# QuadroRiser.net
KiCad netlist of a schematic drawn in Altium Designer
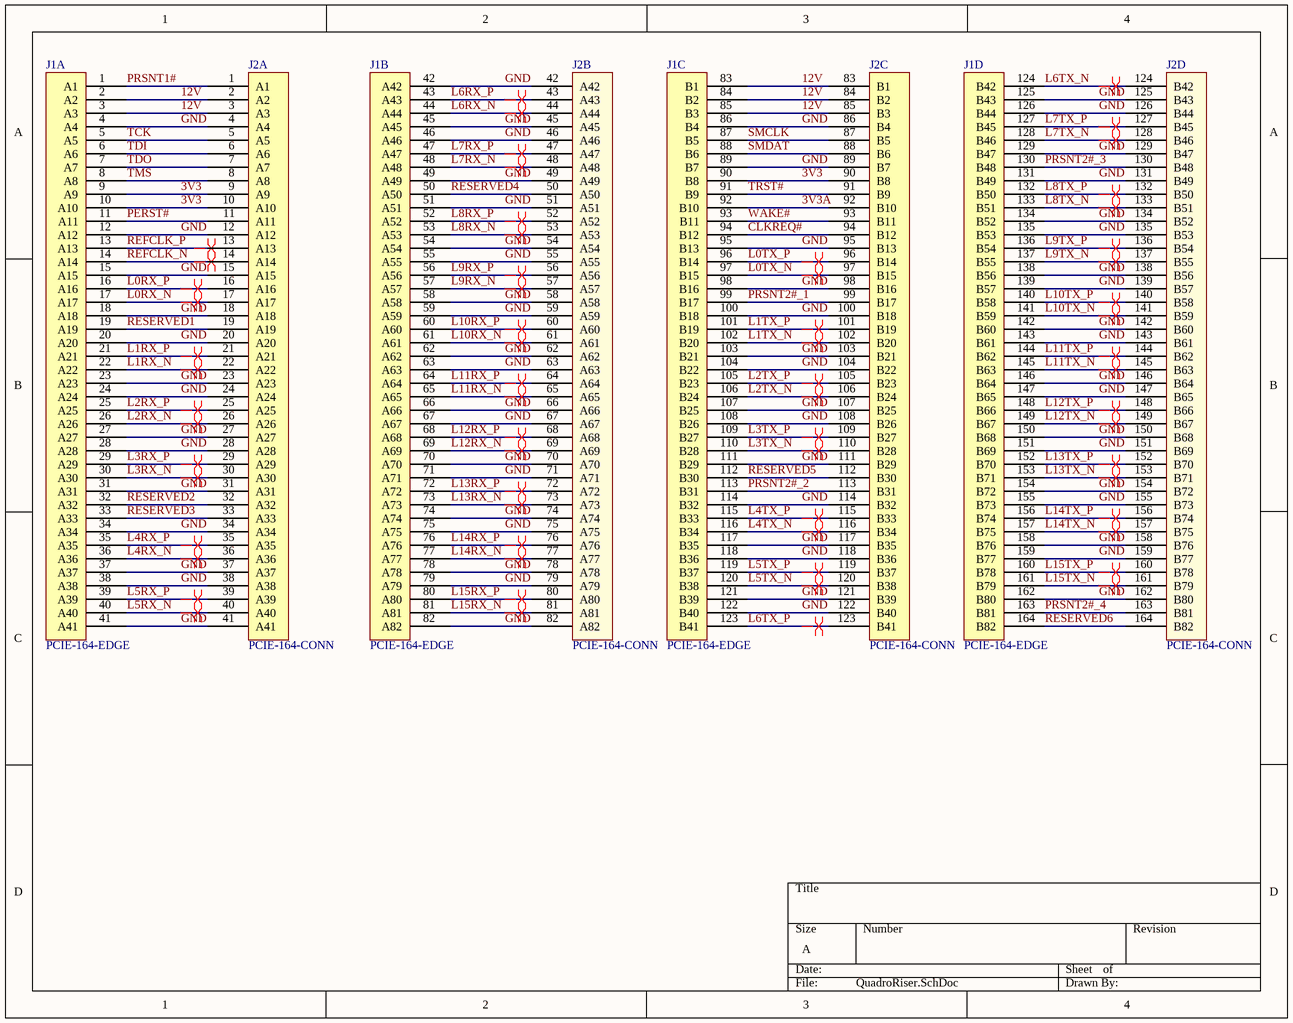
[diagram p0: QuadroRiser.SchDoc]

(export (version "E")
  (design (tool "Eeschema 10.0.6"))
  (components
    (comp (ref "J1")
      (value "PCIE-164-EDGE")
      (footprint "PCIE-164-EDGE")
      (description "PCIe x16 Edge Connector pad layout")
      (libsource (lib "") (part "PCIE-164-EDGE_1"))
    )
    (comp (ref "J2")
      (value "PCIE-164-CONN")
      (footprint "PCIe-164-CONN")
      (description "CONN PCI EXP FEMALE 164POS 0.039")
      (libsource (lib "Connectors") (part "PCIE-164-CONN"))
    )
  )
  (nets
    (net (code "1") (name "/3V3") (class "Default")
      (node (ref "J1") (pin "10") (pinfunction "A10_10") (pintype "passive"))
      (node (ref "J1") (pin "9") (pinfunction "A9_9") (pintype "passive"))
      (node (ref "J1") (pin "90") (pinfunction "B8_90") (pintype "passive"))
      (node (ref "J2") (pin "10") (pinfunction "A10_10") (pintype "passive"))
      (node (ref "J2") (pin "9") (pinfunction "A9_9") (pintype "passive"))
      (node (ref "J2") (pin "90") (pinfunction "B8_90") (pintype "passive"))
    )
    (net (code "2") (name "/3V3A") (class "Default")
      (node (ref "J1") (pin "92") (pinfunction "B10_92") (pintype "passive"))
      (node (ref "J2") (pin "92") (pinfunction "B10_92") (pintype "passive"))
    )
    (net (code "3") (name "/12V") (class "Default")
      (node (ref "J1") (pin "2") (pinfunction "A2_2") (pintype "passive"))
      (node (ref "J1") (pin "3") (pinfunction "A3_3") (pintype "passive"))
      (node (ref "J1") (pin "83") (pinfunction "B1_83") (pintype "passive"))
      (node (ref "J1") (pin "84") (pinfunction "B2_84") (pintype "passive"))
      (node (ref "J1") (pin "85") (pinfunction "B3_85") (pintype "passive"))
      (node (ref "J2") (pin "2") (pinfunction "A2_2") (pintype "passive"))
      (node (ref "J2") (pin "3") (pinfunction "A3_3") (pintype "passive"))
      (node (ref "J2") (pin "83") (pinfunction "B1_83") (pintype "passive"))
      (node (ref "J2") (pin "84") (pinfunction "B2_84") (pintype "passive"))
      (node (ref "J2") (pin "85") (pinfunction "B3_85") (pintype "passive"))
    )
    (net (code "4") (name "/CLKREQ#") (class "Default")
      (node (ref "J1") (pin "94") (pinfunction "B12_94") (pintype "passive"))
      (node (ref "J2") (pin "94") (pinfunction "B12_94") (pintype "passive"))
    )
    (net (code "5") (name "/GND") (class "Default")
      (node (ref "J1") (pin "100") (pinfunction "B18_100") (pintype "passive"))
      (node (ref "J1") (pin "103") (pinfunction "B21_103") (pintype "passive"))
      (node (ref "J1") (pin "104") (pinfunction "B22_104") (pintype "passive"))
      (node (ref "J1") (pin "107") (pinfunction "B25_107") (pintype "passive"))
      (node (ref "J1") (pin "108") (pinfunction "B26_108") (pintype "passive"))
      (node (ref "J1") (pin "111") (pinfunction "B29_111") (pintype "passive"))
      (node (ref "J1") (pin "114") (pinfunction "B32_114") (pintype "passive"))
      (node (ref "J1") (pin "117") (pinfunction "B35_117") (pintype "passive"))
      (node (ref "J1") (pin "118") (pinfunction "B36_118") (pintype "passive"))
      (node (ref "J1") (pin "12") (pinfunction "A12_12") (pintype "passive"))
      (node (ref "J1") (pin "121") (pinfunction "B39_121") (pintype "passive"))
      (node (ref "J1") (pin "122") (pinfunction "B40_122") (pintype "passive"))
      (node (ref "J1") (pin "125") (pinfunction "B43_125") (pintype "passive"))
      (node (ref "J1") (pin "126") (pinfunction "B44_126") (pintype "passive"))
      (node (ref "J1") (pin "129") (pinfunction "B47_129") (pintype "passive"))
      (node (ref "J1") (pin "131") (pinfunction "B49_131") (pintype "passive"))
      (node (ref "J1") (pin "134") (pinfunction "B52_134") (pintype "passive"))
      (node (ref "J1") (pin "135") (pinfunction "B53_135") (pintype "passive"))
      (node (ref "J1") (pin "138") (pinfunction "B56_138") (pintype "passive"))
      (node (ref "J1") (pin "139") (pinfunction "B57_139") (pintype "passive"))
      (node (ref "J1") (pin "142") (pinfunction "B60_142") (pintype "passive"))
      (node (ref "J1") (pin "143") (pinfunction "B61_143") (pintype "passive"))
      (node (ref "J1") (pin "146") (pinfunction "B64_146") (pintype "passive"))
      (node (ref "J1") (pin "147") (pinfunction "B65_147") (pintype "passive"))
      (node (ref "J1") (pin "15") (pinfunction "A15_15") (pintype "passive"))
      (node (ref "J1") (pin "150") (pinfunction "B68_150") (pintype "passive"))
      (node (ref "J1") (pin "151") (pinfunction "B69_151") (pintype "passive"))
      (node (ref "J1") (pin "154") (pinfunction "B72_154") (pintype "passive"))
      (node (ref "J1") (pin "155") (pinfunction "B73_155") (pintype "passive"))
      (node (ref "J1") (pin "158") (pinfunction "B76_158") (pintype "passive"))
      (node (ref "J1") (pin "159") (pinfunction "B77_159") (pintype "passive"))
      (node (ref "J1") (pin "162") (pinfunction "B80_162") (pintype "passive"))
      (node (ref "J1") (pin "18") (pinfunction "A18_18") (pintype "passive"))
      (node (ref "J1") (pin "20") (pinfunction "A20_20") (pintype "passive"))
      (node (ref "J1") (pin "23") (pinfunction "A23_23") (pintype "passive"))
      (node (ref "J1") (pin "24") (pinfunction "A24_24") (pintype "passive"))
      (node (ref "J1") (pin "27") (pinfunction "A27_27") (pintype "passive"))
      (node (ref "J1") (pin "28") (pinfunction "A28_28") (pintype "passive"))
      (node (ref "J1") (pin "31") (pinfunction "A31_31") (pintype "passive"))
      (node (ref "J1") (pin "34") (pinfunction "A34_34") (pintype "passive"))
      (node (ref "J1") (pin "37") (pinfunction "A37_37") (pintype "passive"))
      (node (ref "J1") (pin "38") (pinfunction "A38_38") (pintype "passive"))
      (node (ref "J1") (pin "4") (pinfunction "A4_4") (pintype "passive"))
      (node (ref "J1") (pin "41") (pinfunction "A41_41") (pintype "passive"))
      (node (ref "J1") (pin "42") (pinfunction "A42_42") (pintype "passive"))
      (node (ref "J1") (pin "45") (pinfunction "A45_45") (pintype "passive"))
      (node (ref "J1") (pin "46") (pinfunction "A46_46") (pintype "passive"))
      (node (ref "J1") (pin "49") (pinfunction "A49_49") (pintype "passive"))
      (node (ref "J1") (pin "51") (pinfunction "A51_51") (pintype "passive"))
      (node (ref "J1") (pin "54") (pinfunction "A54_54") (pintype "passive"))
      (node (ref "J1") (pin "55") (pinfunction "A55_55") (pintype "passive"))
      (node (ref "J1") (pin "58") (pinfunction "A58_58") (pintype "passive"))
      (node (ref "J1") (pin "59") (pinfunction "A59_59") (pintype "passive"))
      (node (ref "J1") (pin "62") (pinfunction "A62_62") (pintype "passive"))
      (node (ref "J1") (pin "63") (pinfunction "A63_63") (pintype "passive"))
      (node (ref "J1") (pin "66") (pinfunction "A66_66") (pintype "passive"))
      (node (ref "J1") (pin "67") (pinfunction "A67_67") (pintype "passive"))
      (node (ref "J1") (pin "70") (pinfunction "A70_70") (pintype "passive"))
      (node (ref "J1") (pin "71") (pinfunction "A71_71") (pintype "passive"))
      (node (ref "J1") (pin "74") (pinfunction "A74_74") (pintype "passive"))
      (node (ref "J1") (pin "75") (pinfunction "A75_75") (pintype "passive"))
      (node (ref "J1") (pin "78") (pinfunction "A78_78") (pintype "passive"))
      (node (ref "J1") (pin "79") (pinfunction "A79_79") (pintype "passive"))
      (node (ref "J1") (pin "82") (pinfunction "A82_82") (pintype "passive"))
      (node (ref "J1") (pin "86") (pinfunction "B4_86") (pintype "passive"))
      (node (ref "J1") (pin "89") (pinfunction "B7_89") (pintype "passive"))
      (node (ref "J1") (pin "95") (pinfunction "B13_95") (pintype "passive"))
      (node (ref "J1") (pin "98") (pinfunction "B16_98") (pintype "passive"))
      (node (ref "J2") (pin "100") (pinfunction "B18_100") (pintype "passive"))
      (node (ref "J2") (pin "103") (pinfunction "B21_103") (pintype "passive"))
      (node (ref "J2") (pin "104") (pinfunction "B22_104") (pintype "passive"))
      (node (ref "J2") (pin "107") (pinfunction "B25_107") (pintype "passive"))
      (node (ref "J2") (pin "108") (pinfunction "B26_108") (pintype "passive"))
      (node (ref "J2") (pin "111") (pinfunction "B29_111") (pintype "passive"))
      (node (ref "J2") (pin "114") (pinfunction "B32_114") (pintype "passive"))
      (node (ref "J2") (pin "117") (pinfunction "B35_117") (pintype "passive"))
      (node (ref "J2") (pin "118") (pinfunction "B36_118") (pintype "passive"))
      (node (ref "J2") (pin "12") (pinfunction "A12_12") (pintype "passive"))
      (node (ref "J2") (pin "121") (pinfunction "B39_121") (pintype "passive"))
      (node (ref "J2") (pin "122") (pinfunction "B40_122") (pintype "passive"))
      (node (ref "J2") (pin "125") (pinfunction "B43_125") (pintype "passive"))
      (node (ref "J2") (pin "126") (pinfunction "B44_126") (pintype "passive"))
      (node (ref "J2") (pin "129") (pinfunction "B47_129") (pintype "passive"))
      (node (ref "J2") (pin "131") (pinfunction "B49_131") (pintype "passive"))
      (node (ref "J2") (pin "134") (pinfunction "B52_134") (pintype "passive"))
      (node (ref "J2") (pin "135") (pinfunction "B53_135") (pintype "passive"))
      (node (ref "J2") (pin "138") (pinfunction "B56_138") (pintype "passive"))
      (node (ref "J2") (pin "139") (pinfunction "B57_139") (pintype "passive"))
      (node (ref "J2") (pin "142") (pinfunction "B60_142") (pintype "passive"))
      (node (ref "J2") (pin "143") (pinfunction "B61_143") (pintype "passive"))
      (node (ref "J2") (pin "146") (pinfunction "B64_146") (pintype "passive"))
      (node (ref "J2") (pin "147") (pinfunction "B65_147") (pintype "passive"))
      (node (ref "J2") (pin "15") (pinfunction "A15_15") (pintype "passive"))
      (node (ref "J2") (pin "150") (pinfunction "B68_150") (pintype "passive"))
      (node (ref "J2") (pin "151") (pinfunction "B69_151") (pintype "passive"))
      (node (ref "J2") (pin "154") (pinfunction "B72_154") (pintype "passive"))
      (node (ref "J2") (pin "155") (pinfunction "B73_155") (pintype "passive"))
      (node (ref "J2") (pin "158") (pinfunction "B76_158") (pintype "passive"))
      (node (ref "J2") (pin "159") (pinfunction "B77_159") (pintype "passive"))
      (node (ref "J2") (pin "162") (pinfunction "B80_162") (pintype "passive"))
      (node (ref "J2") (pin "18") (pinfunction "A18_18") (pintype "passive"))
      (node (ref "J2") (pin "20") (pinfunction "A20_20") (pintype "passive"))
      (node (ref "J2") (pin "23") (pinfunction "A23_23") (pintype "passive"))
      (node (ref "J2") (pin "24") (pinfunction "A24_24") (pintype "passive"))
      (node (ref "J2") (pin "27") (pinfunction "A27_27") (pintype "passive"))
      (node (ref "J2") (pin "28") (pinfunction "A28_28") (pintype "passive"))
      (node (ref "J2") (pin "31") (pinfunction "A31_31") (pintype "passive"))
      (node (ref "J2") (pin "34") (pinfunction "A34_34") (pintype "passive"))
      (node (ref "J2") (pin "37") (pinfunction "A37_37") (pintype "passive"))
      (node (ref "J2") (pin "38") (pinfunction "A38_38") (pintype "passive"))
      (node (ref "J2") (pin "4") (pinfunction "A4_4") (pintype "passive"))
      (node (ref "J2") (pin "41") (pinfunction "A41_41") (pintype "passive"))
      (node (ref "J2") (pin "42") (pinfunction "A42_42") (pintype "passive"))
      (node (ref "J2") (pin "45") (pinfunction "A45_45") (pintype "passive"))
      (node (ref "J2") (pin "46") (pinfunction "A46_46") (pintype "passive"))
      (node (ref "J2") (pin "49") (pinfunction "A49_49") (pintype "passive"))
      (node (ref "J2") (pin "51") (pinfunction "A51_51") (pintype "passive"))
      (node (ref "J2") (pin "54") (pinfunction "A54_54") (pintype "passive"))
      (node (ref "J2") (pin "55") (pinfunction "A55_55") (pintype "passive"))
      (node (ref "J2") (pin "58") (pinfunction "A58_58") (pintype "passive"))
      (node (ref "J2") (pin "59") (pinfunction "A59_59") (pintype "passive"))
      (node (ref "J2") (pin "62") (pinfunction "A62_62") (pintype "passive"))
      (node (ref "J2") (pin "63") (pinfunction "A63_63") (pintype "passive"))
      (node (ref "J2") (pin "66") (pinfunction "A66_66") (pintype "passive"))
      (node (ref "J2") (pin "67") (pinfunction "A67_67") (pintype "passive"))
      (node (ref "J2") (pin "70") (pinfunction "A70_70") (pintype "passive"))
      (node (ref "J2") (pin "71") (pinfunction "A71_71") (pintype "passive"))
      (node (ref "J2") (pin "74") (pinfunction "A74_74") (pintype "passive"))
      (node (ref "J2") (pin "75") (pinfunction "A75_75") (pintype "passive"))
      (node (ref "J2") (pin "78") (pinfunction "A78_78") (pintype "passive"))
      (node (ref "J2") (pin "79") (pinfunction "A79_79") (pintype "passive"))
      (node (ref "J2") (pin "82") (pinfunction "A82_82") (pintype "passive"))
      (node (ref "J2") (pin "86") (pinfunction "B4_86") (pintype "passive"))
      (node (ref "J2") (pin "89") (pinfunction "B7_89") (pintype "passive"))
      (node (ref "J2") (pin "95") (pinfunction "B13_95") (pintype "passive"))
      (node (ref "J2") (pin "98") (pinfunction "B16_98") (pintype "passive"))
    )
    (net (code "6") (name "/L0RX_N") (class "Default")
      (node (ref "J1") (pin "17") (pinfunction "A17_17") (pintype "passive"))
      (node (ref "J2") (pin "17") (pinfunction "A17_17") (pintype "passive"))
    )
    (net (code "7") (name "/L0RX_P") (class "Default")
      (node (ref "J1") (pin "16") (pinfunction "A16_16") (pintype "passive"))
      (node (ref "J2") (pin "16") (pinfunction "A16_16") (pintype "passive"))
    )
    (net (code "8") (name "/L0TX_N") (class "Default")
      (node (ref "J1") (pin "97") (pinfunction "B15_97") (pintype "passive"))
      (node (ref "J2") (pin "97") (pinfunction "B15_97") (pintype "passive"))
    )
    (net (code "9") (name "/L0TX_P") (class "Default")
      (node (ref "J1") (pin "96") (pinfunction "B14_96") (pintype "passive"))
      (node (ref "J2") (pin "96") (pinfunction "B14_96") (pintype "passive"))
    )
    (net (code "10") (name "/L1RX_N") (class "Default")
      (node (ref "J1") (pin "22") (pinfunction "A22_22") (pintype "passive"))
      (node (ref "J2") (pin "22") (pinfunction "A22_22") (pintype "passive"))
    )
    (net (code "11") (name "/L1RX_P") (class "Default")
      (node (ref "J1") (pin "21") (pinfunction "A21_21") (pintype "passive"))
      (node (ref "J2") (pin "21") (pinfunction "A21_21") (pintype "passive"))
    )
    (net (code "12") (name "/L1TX_N") (class "Default")
      (node (ref "J1") (pin "102") (pinfunction "B20_102") (pintype "passive"))
      (node (ref "J2") (pin "102") (pinfunction "B20_102") (pintype "passive"))
    )
    (net (code "13") (name "/L1TX_P") (class "Default")
      (node (ref "J1") (pin "101") (pinfunction "B19_101") (pintype "passive"))
      (node (ref "J2") (pin "101") (pinfunction "B19_101") (pintype "passive"))
    )
    (net (code "14") (name "/L2RX_N") (class "Default")
      (node (ref "J1") (pin "26") (pinfunction "A26_26") (pintype "passive"))
      (node (ref "J2") (pin "26") (pinfunction "A26_26") (pintype "passive"))
    )
    (net (code "15") (name "/L2RX_P") (class "Default")
      (node (ref "J1") (pin "25") (pinfunction "A25_25") (pintype "passive"))
      (node (ref "J2") (pin "25") (pinfunction "A25_25") (pintype "passive"))
    )
    (net (code "16") (name "/L2TX_N") (class "Default")
      (node (ref "J1") (pin "106") (pinfunction "B24_106") (pintype "passive"))
      (node (ref "J2") (pin "106") (pinfunction "B24_106") (pintype "passive"))
    )
    (net (code "17") (name "/L2TX_P") (class "Default")
      (node (ref "J1") (pin "105") (pinfunction "B23_105") (pintype "passive"))
      (node (ref "J2") (pin "105") (pinfunction "B23_105") (pintype "passive"))
    )
    (net (code "18") (name "/L3RX_N") (class "Default")
      (node (ref "J1") (pin "30") (pinfunction "A30_30") (pintype "passive"))
      (node (ref "J2") (pin "30") (pinfunction "A30_30") (pintype "passive"))
    )
    (net (code "19") (name "/L3RX_P") (class "Default")
      (node (ref "J1") (pin "29") (pinfunction "A29_29") (pintype "passive"))
      (node (ref "J2") (pin "29") (pinfunction "A29_29") (pintype "passive"))
    )
    (net (code "20") (name "/L3TX_N") (class "Default")
      (node (ref "J1") (pin "110") (pinfunction "B28_110") (pintype "passive"))
      (node (ref "J2") (pin "110") (pinfunction "B28_110") (pintype "passive"))
    )
    (net (code "21") (name "/L3TX_P") (class "Default")
      (node (ref "J1") (pin "109") (pinfunction "B27_109") (pintype "passive"))
      (node (ref "J2") (pin "109") (pinfunction "B27_109") (pintype "passive"))
    )
    (net (code "22") (name "/L4RX_N") (class "Default")
      (node (ref "J1") (pin "36") (pinfunction "A36_36") (pintype "passive"))
      (node (ref "J2") (pin "36") (pinfunction "A36_36") (pintype "passive"))
    )
    (net (code "23") (name "/L4RX_P") (class "Default")
      (node (ref "J1") (pin "35") (pinfunction "A35_35") (pintype "passive"))
      (node (ref "J2") (pin "35") (pinfunction "A35_35") (pintype "passive"))
    )
    (net (code "24") (name "/L4TX_N") (class "Default")
      (node (ref "J1") (pin "116") (pinfunction "B34_116") (pintype "passive"))
      (node (ref "J2") (pin "116") (pinfunction "B34_116") (pintype "passive"))
    )
    (net (code "25") (name "/L4TX_P") (class "Default")
      (node (ref "J1") (pin "115") (pinfunction "B33_115") (pintype "passive"))
      (node (ref "J2") (pin "115") (pinfunction "B33_115") (pintype "passive"))
    )
    (net (code "26") (name "/L5RX_N") (class "Default")
      (node (ref "J1") (pin "40") (pinfunction "A40_40") (pintype "passive"))
      (node (ref "J2") (pin "40") (pinfunction "A40_40") (pintype "passive"))
    )
    (net (code "27") (name "/L5RX_P") (class "Default")
      (node (ref "J1") (pin "39") (pinfunction "A39_39") (pintype "passive"))
      (node (ref "J2") (pin "39") (pinfunction "A39_39") (pintype "passive"))
    )
    (net (code "28") (name "/L5TX_N") (class "Default")
      (node (ref "J1") (pin "120") (pinfunction "B38_120") (pintype "passive"))
      (node (ref "J2") (pin "120") (pinfunction "B38_120") (pintype "passive"))
    )
    (net (code "29") (name "/L5TX_P") (class "Default")
      (node (ref "J1") (pin "119") (pinfunction "B37_119") (pintype "passive"))
      (node (ref "J2") (pin "119") (pinfunction "B37_119") (pintype "passive"))
    )
    (net (code "30") (name "/L6RX_N") (class "Default")
      (node (ref "J1") (pin "44") (pinfunction "A44_44") (pintype "passive"))
      (node (ref "J2") (pin "44") (pinfunction "A44_44") (pintype "passive"))
    )
    (net (code "31") (name "/L6RX_P") (class "Default")
      (node (ref "J1") (pin "43") (pinfunction "A43_43") (pintype "passive"))
      (node (ref "J2") (pin "43") (pinfunction "A43_43") (pintype "passive"))
    )
    (net (code "32") (name "/L6TX_N") (class "Default")
      (node (ref "J1") (pin "124") (pinfunction "B42_124") (pintype "passive"))
      (node (ref "J2") (pin "124") (pinfunction "B42_124") (pintype "passive"))
    )
    (net (code "33") (name "/L6TX_P") (class "Default")
      (node (ref "J1") (pin "123") (pinfunction "B41_123") (pintype "passive"))
      (node (ref "J2") (pin "123") (pinfunction "B41_123") (pintype "passive"))
    )
    (net (code "34") (name "/L7RX_N") (class "Default")
      (node (ref "J1") (pin "48") (pinfunction "A48_48") (pintype "passive"))
      (node (ref "J2") (pin "48") (pinfunction "A48_48") (pintype "passive"))
    )
    (net (code "35") (name "/L7RX_P") (class "Default")
      (node (ref "J1") (pin "47") (pinfunction "A47_47") (pintype "passive"))
      (node (ref "J2") (pin "47") (pinfunction "A47_47") (pintype "passive"))
    )
    (net (code "36") (name "/L7TX_N") (class "Default")
      (node (ref "J1") (pin "128") (pinfunction "B46_128") (pintype "passive"))
      (node (ref "J2") (pin "128") (pinfunction "B46_128") (pintype "passive"))
    )
    (net (code "37") (name "/L7TX_P") (class "Default")
      (node (ref "J1") (pin "127") (pinfunction "B45_127") (pintype "passive"))
      (node (ref "J2") (pin "127") (pinfunction "B45_127") (pintype "passive"))
    )
    (net (code "38") (name "/L8RX_N") (class "Default")
      (node (ref "J1") (pin "53") (pinfunction "A53_53") (pintype "passive"))
      (node (ref "J2") (pin "53") (pinfunction "A53_53") (pintype "passive"))
    )
    (net (code "39") (name "/L8RX_P") (class "Default")
      (node (ref "J1") (pin "52") (pinfunction "A52_52") (pintype "passive"))
      (node (ref "J2") (pin "52") (pinfunction "A52_52") (pintype "passive"))
    )
    (net (code "40") (name "/L8TX_N") (class "Default")
      (node (ref "J1") (pin "133") (pinfunction "B51_133") (pintype "passive"))
      (node (ref "J2") (pin "133") (pinfunction "B51_133") (pintype "passive"))
    )
    (net (code "41") (name "/L8TX_P") (class "Default")
      (node (ref "J1") (pin "132") (pinfunction "B50_132") (pintype "passive"))
      (node (ref "J2") (pin "132") (pinfunction "B50_132") (pintype "passive"))
    )
    (net (code "42") (name "/L9RX_N") (class "Default")
      (node (ref "J1") (pin "57") (pinfunction "A57_57") (pintype "passive"))
      (node (ref "J2") (pin "57") (pinfunction "A57_57") (pintype "passive"))
    )
    (net (code "43") (name "/L9RX_P") (class "Default")
      (node (ref "J1") (pin "56") (pinfunction "A56_56") (pintype "passive"))
      (node (ref "J2") (pin "56") (pinfunction "A56_56") (pintype "passive"))
    )
    (net (code "44") (name "/L9TX_N") (class "Default")
      (node (ref "J1") (pin "137") (pinfunction "B55_137") (pintype "passive"))
      (node (ref "J2") (pin "137") (pinfunction "B55_137") (pintype "passive"))
    )
    (net (code "45") (name "/L9TX_P") (class "Default")
      (node (ref "J1") (pin "136") (pinfunction "B54_136") (pintype "passive"))
      (node (ref "J2") (pin "136") (pinfunction "B54_136") (pintype "passive"))
    )
    (net (code "46") (name "/L10RX_N") (class "Default")
      (node (ref "J1") (pin "61") (pinfunction "A61_61") (pintype "passive"))
      (node (ref "J2") (pin "61") (pinfunction "A61_61") (pintype "passive"))
    )
    (net (code "47") (name "/L10RX_P") (class "Default")
      (node (ref "J1") (pin "60") (pinfunction "A60_60") (pintype "passive"))
      (node (ref "J2") (pin "60") (pinfunction "A60_60") (pintype "passive"))
    )
    (net (code "48") (name "/L10TX_N") (class "Default")
      (node (ref "J1") (pin "141") (pinfunction "B59_141") (pintype "passive"))
      (node (ref "J2") (pin "141") (pinfunction "B59_141") (pintype "passive"))
    )
    (net (code "49") (name "/L10TX_P") (class "Default")
      (node (ref "J1") (pin "140") (pinfunction "B58_140") (pintype "passive"))
      (node (ref "J2") (pin "140") (pinfunction "B58_140") (pintype "passive"))
    )
    (net (code "50") (name "/L11RX_N") (class "Default")
      (node (ref "J1") (pin "65") (pinfunction "A65_65") (pintype "passive"))
      (node (ref "J2") (pin "65") (pinfunction "A65_65") (pintype "passive"))
    )
    (net (code "51") (name "/L11RX_P") (class "Default")
      (node (ref "J1") (pin "64") (pinfunction "A64_64") (pintype "passive"))
      (node (ref "J2") (pin "64") (pinfunction "A64_64") (pintype "passive"))
    )
    (net (code "52") (name "/L11TX_N") (class "Default")
      (node (ref "J1") (pin "145") (pinfunction "B63_145") (pintype "passive"))
      (node (ref "J2") (pin "145") (pinfunction "B63_145") (pintype "passive"))
    )
    (net (code "53") (name "/L11TX_P") (class "Default")
      (node (ref "J1") (pin "144") (pinfunction "B62_144") (pintype "passive"))
      (node (ref "J2") (pin "144") (pinfunction "B62_144") (pintype "passive"))
    )
    (net (code "54") (name "/L12RX_N") (class "Default")
      (node (ref "J1") (pin "69") (pinfunction "A69_69") (pintype "passive"))
      (node (ref "J2") (pin "69") (pinfunction "A69_69") (pintype "passive"))
    )
    (net (code "55") (name "/L12RX_P") (class "Default")
      (node (ref "J1") (pin "68") (pinfunction "A68_68") (pintype "passive"))
      (node (ref "J2") (pin "68") (pinfunction "A68_68") (pintype "passive"))
    )
    (net (code "56") (name "/L12TX_N") (class "Default")
      (node (ref "J1") (pin "149") (pinfunction "B67_149") (pintype "passive"))
      (node (ref "J2") (pin "149") (pinfunction "B67_149") (pintype "passive"))
    )
    (net (code "57") (name "/L12TX_P") (class "Default")
      (node (ref "J1") (pin "148") (pinfunction "B66_148") (pintype "passive"))
      (node (ref "J2") (pin "148") (pinfunction "B66_148") (pintype "passive"))
    )
    (net (code "58") (name "/L13RX_N") (class "Default")
      (node (ref "J1") (pin "73") (pinfunction "A73_73") (pintype "passive"))
      (node (ref "J2") (pin "73") (pinfunction "A73_73") (pintype "passive"))
    )
    (net (code "59") (name "/L13RX_P") (class "Default")
      (node (ref "J1") (pin "72") (pinfunction "A72_72") (pintype "passive"))
      (node (ref "J2") (pin "72") (pinfunction "A72_72") (pintype "passive"))
    )
    (net (code "60") (name "/L13TX_N") (class "Default")
      (node (ref "J1") (pin "153") (pinfunction "B71_153") (pintype "passive"))
      (node (ref "J2") (pin "153") (pinfunction "B71_153") (pintype "passive"))
    )
    (net (code "61") (name "/L13TX_P") (class "Default")
      (node (ref "J1") (pin "152") (pinfunction "B70_152") (pintype "passive"))
      (node (ref "J2") (pin "152") (pinfunction "B70_152") (pintype "passive"))
    )
    (net (code "62") (name "/L14RX_N") (class "Default")
      (node (ref "J1") (pin "77") (pinfunction "A77_77") (pintype "passive"))
      (node (ref "J2") (pin "77") (pinfunction "A77_77") (pintype "passive"))
    )
    (net (code "63") (name "/L14RX_P") (class "Default")
      (node (ref "J1") (pin "76") (pinfunction "A76_76") (pintype "passive"))
      (node (ref "J2") (pin "76") (pinfunction "A76_76") (pintype "passive"))
    )
    (net (code "64") (name "/L14TX_N") (class "Default")
      (node (ref "J1") (pin "157") (pinfunction "B75_157") (pintype "passive"))
      (node (ref "J2") (pin "157") (pinfunction "B75_157") (pintype "passive"))
    )
    (net (code "65") (name "/L14TX_P") (class "Default")
      (node (ref "J1") (pin "156") (pinfunction "B74_156") (pintype "passive"))
      (node (ref "J2") (pin "156") (pinfunction "B74_156") (pintype "passive"))
    )
    (net (code "66") (name "/L15RX_N") (class "Default")
      (node (ref "J1") (pin "81") (pinfunction "A81_81") (pintype "passive"))
      (node (ref "J2") (pin "81") (pinfunction "A81_81") (pintype "passive"))
    )
    (net (code "67") (name "/L15RX_P") (class "Default")
      (node (ref "J1") (pin "80") (pinfunction "A80_80") (pintype "passive"))
      (node (ref "J2") (pin "80") (pinfunction "A80_80") (pintype "passive"))
    )
    (net (code "68") (name "/L15TX_N") (class "Default")
      (node (ref "J1") (pin "161") (pinfunction "B79_161") (pintype "passive"))
      (node (ref "J2") (pin "161") (pinfunction "B79_161") (pintype "passive"))
    )
    (net (code "69") (name "/L15TX_P") (class "Default")
      (node (ref "J1") (pin "160") (pinfunction "B78_160") (pintype "passive"))
      (node (ref "J2") (pin "160") (pinfunction "B78_160") (pintype "passive"))
    )
    (net (code "70") (name "/PERST#") (class "Default")
      (node (ref "J1") (pin "11") (pinfunction "A11_11") (pintype "passive"))
      (node (ref "J2") (pin "11") (pinfunction "A11_11") (pintype "passive"))
    )
    (net (code "71") (name "/PRSNT1#") (class "Default")
      (node (ref "J1") (pin "1") (pinfunction "A1_1") (pintype "passive"))
      (node (ref "J2") (pin "1") (pinfunction "A1_1") (pintype "passive"))
    )
    (net (code "72") (name "/PRSNT2#_1") (class "Default")
      (node (ref "J1") (pin "99") (pinfunction "B17_99") (pintype "passive"))
      (node (ref "J2") (pin "99") (pinfunction "B17_99") (pintype "passive"))
    )
    (net (code "73") (name "/PRSNT2#_2") (class "Default")
      (node (ref "J1") (pin "113") (pinfunction "B31_113") (pintype "passive"))
      (node (ref "J2") (pin "113") (pinfunction "B31_113") (pintype "passive"))
    )
    (net (code "74") (name "/PRSNT2#_3") (class "Default")
      (node (ref "J1") (pin "130") (pinfunction "B48_130") (pintype "passive"))
      (node (ref "J2") (pin "130") (pinfunction "B48_130") (pintype "passive"))
    )
    (net (code "75") (name "/PRSNT2#_4") (class "Default")
      (node (ref "J1") (pin "163") (pinfunction "B81_163") (pintype "passive"))
      (node (ref "J2") (pin "163") (pinfunction "B81_163") (pintype "passive"))
    )
    (net (code "76") (name "/REFCLK_N") (class "Default")
      (node (ref "J1") (pin "14") (pinfunction "A14_14") (pintype "passive"))
      (node (ref "J2") (pin "14") (pinfunction "A14_14") (pintype "passive"))
    )
    (net (code "77") (name "/REFCLK_P") (class "Default")
      (node (ref "J1") (pin "13") (pinfunction "A13_13") (pintype "passive"))
      (node (ref "J2") (pin "13") (pinfunction "A13_13") (pintype "passive"))
    )
    (net (code "78") (name "/RESERVED1") (class "Default")
      (node (ref "J1") (pin "19") (pinfunction "A19_19") (pintype "passive"))
      (node (ref "J2") (pin "19") (pinfunction "A19_19") (pintype "passive"))
    )
    (net (code "79") (name "/RESERVED2") (class "Default")
      (node (ref "J1") (pin "32") (pinfunction "A32_32") (pintype "passive"))
      (node (ref "J2") (pin "32") (pinfunction "A32_32") (pintype "passive"))
    )
    (net (code "80") (name "/RESERVED3") (class "Default")
      (node (ref "J1") (pin "33") (pinfunction "A33_33") (pintype "passive"))
      (node (ref "J2") (pin "33") (pinfunction "A33_33") (pintype "passive"))
    )
    (net (code "81") (name "/RESERVED4") (class "Default")
      (node (ref "J1") (pin "50") (pinfunction "A50_50") (pintype "passive"))
      (node (ref "J2") (pin "50") (pinfunction "A50_50") (pintype "passive"))
    )
    (net (code "82") (name "/RESERVED5") (class "Default")
      (node (ref "J1") (pin "112") (pinfunction "B30_112") (pintype "passive"))
      (node (ref "J2") (pin "112") (pinfunction "B30_112") (pintype "passive"))
    )
    (net (code "83") (name "/RESERVED6") (class "Default")
      (node (ref "J1") (pin "164") (pinfunction "B82_164") (pintype "passive"))
      (node (ref "J2") (pin "164") (pinfunction "B82_164") (pintype "passive"))
    )
    (net (code "84") (name "/SMCLK") (class "Default")
      (node (ref "J1") (pin "87") (pinfunction "B5_87") (pintype "passive"))
      (node (ref "J2") (pin "87") (pinfunction "B5_87") (pintype "passive"))
    )
    (net (code "85") (name "/SMDAT") (class "Default")
      (node (ref "J1") (pin "88") (pinfunction "B6_88") (pintype "passive"))
      (node (ref "J2") (pin "88") (pinfunction "B6_88") (pintype "passive"))
    )
    (net (code "86") (name "/TCK") (class "Default")
      (node (ref "J1") (pin "5") (pinfunction "A5_5") (pintype "passive"))
      (node (ref "J2") (pin "5") (pinfunction "A5_5") (pintype "passive"))
    )
    (net (code "87") (name "/TDI") (class "Default")
      (node (ref "J1") (pin "6") (pinfunction "A6_6") (pintype "passive"))
      (node (ref "J2") (pin "6") (pinfunction "A6_6") (pintype "passive"))
    )
    (net (code "88") (name "/TDO") (class "Default")
      (node (ref "J1") (pin "7") (pinfunction "A7_7") (pintype "passive"))
      (node (ref "J2") (pin "7") (pinfunction "A7_7") (pintype "passive"))
    )
    (net (code "89") (name "/TMS") (class "Default")
      (node (ref "J1") (pin "8") (pinfunction "A8_8") (pintype "passive"))
      (node (ref "J2") (pin "8") (pinfunction "A8_8") (pintype "passive"))
    )
    (net (code "90") (name "/TRST#") (class "Default")
      (node (ref "J1") (pin "91") (pinfunction "B9_91") (pintype "passive"))
      (node (ref "J2") (pin "91") (pinfunction "B9_91") (pintype "passive"))
    )
    (net (code "91") (name "/WAKE#") (class "Default")
      (node (ref "J1") (pin "93") (pinfunction "B11_93") (pintype "passive"))
      (node (ref "J2") (pin "93") (pinfunction "B11_93") (pintype "passive"))
    )
  )
)
